# RPL_POWER_24V_REV3.net
KiCad netlist of a schematic drawn in Altium Designer
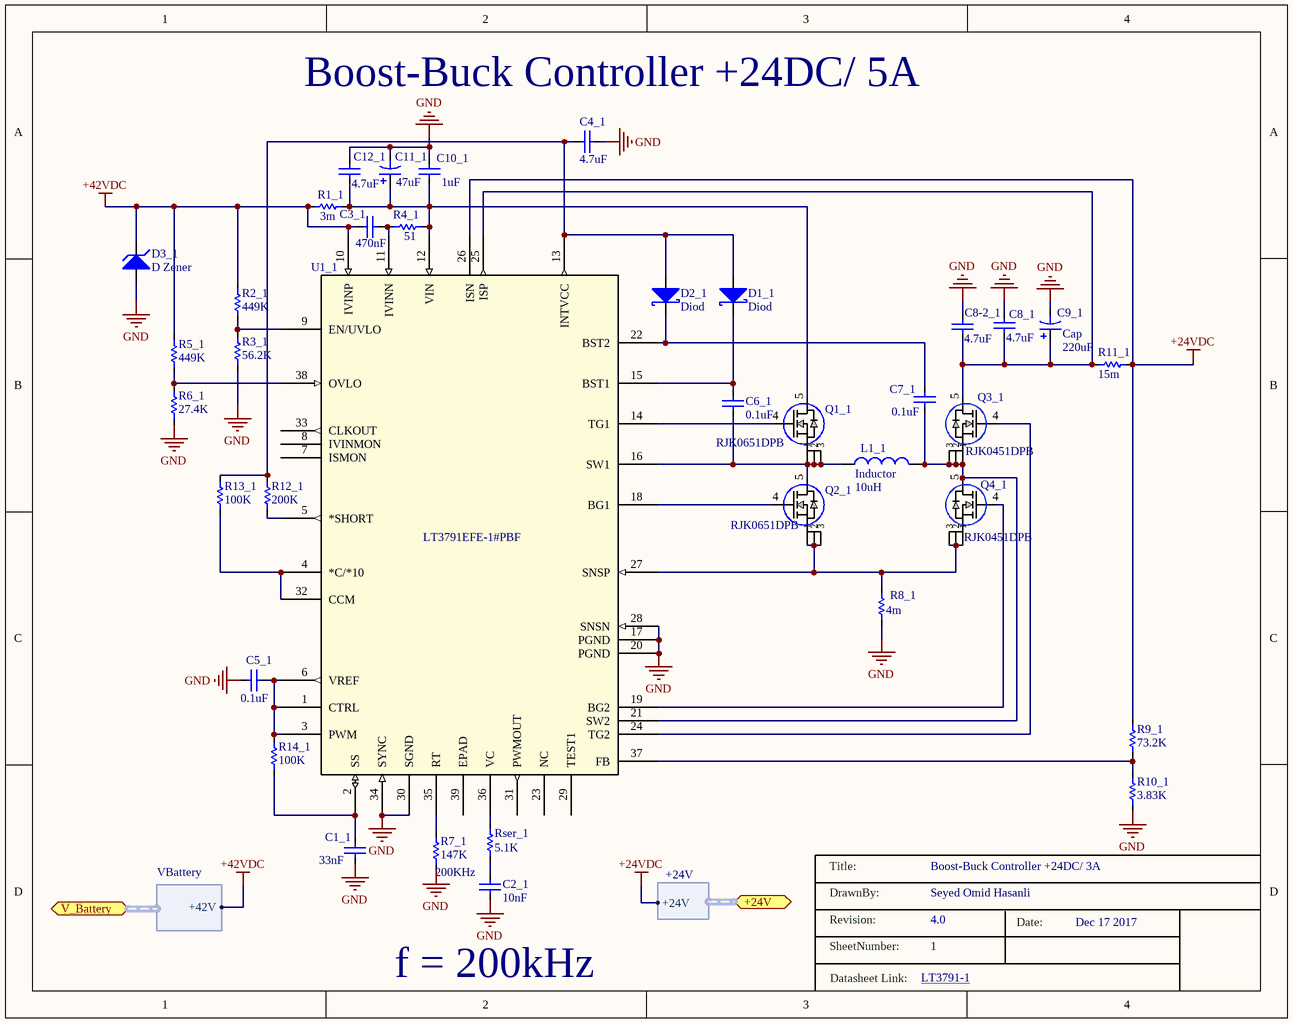
[diagram p0: RPL_POWER_24V_REV3.SchDoc]

(export (version "E")
  (design (tool "Eeschema 10.0.6"))
  (components
    (comp (ref "C1_1")
      (value "33nF")
      (footprint "C1206C475K5PACTU")
      (fields (field (name "Comment") "Cap"))
      (libsource (lib "Generic_Library") (part "Cap"))
    )
    (comp (ref "C2_1")
      (value "10nF")
      (footprint "C0805C475K9RACAUTO")
      (fields (field (name "Comment") "Rser=5.1K"))
      (libsource (lib "Generic_Library") (part "Cap"))
    )
    (comp (ref "C3_1")
      (value "470nF")
      (footprint "CAPs:C0805C475K9RACAUTO")
      (fields (field (name "Comment") "Cap"))
      (libsource (lib "Generic_Library") (part "Cap"))
    )
    (comp (ref "C4_1")
      (value "4.7uF")
      (footprint "CAPs:C0805C475K9RACAUTO")
      (fields (field (name "Comment") "Cap"))
      (libsource (lib "Generic_Library") (part "Cap"))
    )
    (comp (ref "C5_1")
      (value "0.1uF")
      (footprint "CAPs:C0805C475K9RACAUTO")
      (fields (field (name "Comment") "Cap"))
      (libsource (lib "Generic_Library") (part "Cap"))
    )
    (comp (ref "C6_1")
      (value "0.1uF")
      (footprint "CAPs:C0805C475K9RACAUTO")
      (fields (field (name "Comment") "Cap"))
      (libsource (lib "Generic_Library") (part "Cap"))
    )
    (comp (ref "C7_1")
      (value "0.1uF")
      (footprint "CAPs:C0805C475K9RACAUTO")
      (fields (field (name "Comment") "Cap"))
      (libsource (lib "Generic_Library") (part "Cap"))
    )
    (comp (ref "C8-2_1")
      (value "4.7uF")
      (footprint "CAPs:C1206C475K5PACTU")
      (fields (field (name "Comment") "Cap"))
      (libsource (lib "Generic_Library") (part "Cap"))
    )
    (comp (ref "C8_1")
      (value "4.7uF")
      (footprint "CAPs:C1206C475K5PACTU")
      (fields (field (name "Comment") "Cap"))
      (libsource (lib "Generic_Library") (part "Cap"))
    )
    (comp (ref "C9_1")
      (value "Cap")
      (footprint "EEE_FK1V221AP")
      (fields (field (name "ALTIUM_VALUE") "220uF"))
      (libsource (lib "Generic_Library") (part "Cap Elec"))
    )
    (comp (ref "C10_1")
      (value "1uF")
      (footprint "CAPs:C0805C475K9RACAUTO")
      (fields (field (name "Comment") "Cap"))
      (libsource (lib "Generic_Library") (part "Cap"))
    )
    (comp (ref "C11_1")
      (value "47uF")
      (footprint "EEH_ZC1K470P")
      (fields (field (name "Comment") "Cap"))
      (libsource (lib "Generic_Library") (part "Cap Elec"))
    )
    (comp (ref "C12_1")
      (value "4.7uF")
      (footprint "CAPs:C0805C475K9RACAUTO")
      (fields (field (name "Comment") "Cap"))
      (libsource (lib "Generic_Library") (part "Cap"))
    )
    (comp (ref "D1_1")
      (value "Diod")
      (footprint "Diods:SODFL250X80-2N")
      (libsource (lib "Generic_Library") (part "Diod"))
    )
    (comp (ref "D2_1")
      (value "Diod")
      (footprint "Diods:SODFL250X80-2N")
      (libsource (lib "Generic_Library") (part "Diod"))
    )
    (comp (ref "D3_1")
      (value "D Zener")
      (footprint "SMAJ30A-TP")
      (description "Zener Diode")
      (fields (field (name "PUBLISHER") "Altium Limited"))
      (libsource (lib "Generic_Library") (part "D Zener"))
    )
    (comp (ref "L1_1")
      (value "Inductor")
      (footprint "SER1360-103KLB")
      (fields (field (name "ALTIUM_VALUE") "10uH"))
      (libsource (lib "Generic_Library") (part "Inductor"))
    )
    (comp (ref "Q1_1")
      (value "RJK0651DPB")
      (footprint "RJK0651DPB:LFPAK")
      (description "Imported")
      (fields (field (name "MANUFACTURER_PART_NUMBER") "RJK0651DPB-00#J5"))
      (libsource (lib "Generic_Library") (part "RJK0651DPB-00#J5"))
    )
    (comp (ref "Q2_1")
      (value "RJK0651DPB")
      (footprint "RJK0651DPB:LFPAK")
      (description "Imported")
      (fields (field (name "MANUFACTURER_PART_NUMBER") "RJK0651DPB-00#J5"))
      (libsource (lib "Generic_Library") (part "RJK0651DPB-00#J5"))
    )
    (comp (ref "Q3_1")
      (value "RJK0451DPB")
      (footprint "RJK0451DPB:LFPAK")
      (description "Imported")
      (fields (field (name "MANUFACTURER_PART_NUMBER") "RJK0451DPB-00#J5"))
      (libsource (lib "Generic_Library") (part "RJK0451DPB-00#J5"))
    )
    (comp (ref "Q4_1")
      (value "RJK0451DPB")
      (footprint "RJK0451DPB:LFPAK")
      (description "Imported")
      (fields (field (name "MANUFACTURER_PART_NUMBER") "RJK0451DPB-00#J5"))
      (libsource (lib "Generic_Library") (part "RJK0451DPB-00#J5"))
    )
    (comp (ref "R1_1")
      (value "3m")
      (footprint "Resistors:WSL12063L000FEA(1206)")
      (fields (field (name "Comment") "Res"))
      (libsource (lib "Generic_Library") (part "Res"))
    )
    (comp (ref "R2_1")
      (value "449K")
      (footprint "SMD Resistors:RES 0805")
      (fields (field (name "Comment") "Res"))
      (libsource (lib "Generic_Library") (part "Res"))
    )
    (comp (ref "R3_1")
      (value "56.2K")
      (footprint "SMD Resistors:RES 0805")
      (fields (field (name "Comment") "Res"))
      (libsource (lib "Generic_Library") (part "Res"))
    )
    (comp (ref "R4_1")
      (value "51")
      (footprint "SMD Resistors:RES 0805")
      (fields (field (name "Comment") "Res"))
      (libsource (lib "Generic_Library") (part "Res"))
    )
    (comp (ref "R5_1")
      (value "449K")
      (footprint "Resistors:PTN1206E4993BBT1(1206)")
      (fields (field (name "Comment") "Res"))
      (libsource (lib "Generic_Library") (part "Res"))
    )
    (comp (ref "R6_1")
      (value "27.4K")
      (footprint "SMD Resistors:RES 0805")
      (fields (field (name "Comment") "Res"))
      (libsource (lib "Generic_Library") (part "Res"))
    )
    (comp (ref "R7_1")
      (value "200KHz")
      (footprint "SMD Resistors:RES 0805")
      (fields (field (name "ALTIUM_VALUE") "147K"))
      (libsource (lib "Generic_Library") (part "Res"))
    )
    (comp (ref "R8_1")
      (value "4m")
      (footprint "SMD Resistors:RES 0805")
      (fields (field (name "Comment") "Res"))
      (libsource (lib "Generic_Library") (part "Res"))
    )
    (comp (ref "R9_1")
      (value "73.2K")
      (footprint "SMD Resistors:RES 0805")
      (fields (field (name "Comment") "Res"))
      (libsource (lib "Generic_Library") (part "Res"))
    )
    (comp (ref "R10_1")
      (value "3.83K")
      (footprint "SMD Resistors:RES 0805")
      (fields (field (name "Comment") "Res"))
      (libsource (lib "Generic_Library") (part "Res"))
    )
    (comp (ref "R11_1")
      (value "15m")
      (footprint "Resistors:WSL2010R0150FEA(2010)")
      (fields (field (name "Comment") "Res"))
      (libsource (lib "Generic_Library") (part "Res"))
    )
    (comp (ref "R12_1")
      (value "200K")
      (footprint "SMD Resistors:RES 0805")
      (fields (field (name "Comment") "Res"))
      (libsource (lib "Generic_Library") (part "Res"))
    )
    (comp (ref "R13_1")
      (value "100K")
      (footprint "SMD Resistors:RES 0805")
      (fields (field (name "Comment") "Res"))
      (libsource (lib "Generic_Library") (part "Res"))
    )
    (comp (ref "R14_1")
      (value "100K")
      (footprint "SMD Resistors:RES 0805")
      (fields (field (name "Comment") "Res"))
      (libsource (lib "Generic_Library") (part "Res"))
    )
    (comp (ref "Rser_1")
      (value "5.1K")
      (footprint "SMD Resistors:RES 0805")
      (fields (field (name "Comment") "Res"))
      (libsource (lib "Generic_Library") (part "Res"))
    )
    (comp (ref "U1_1")
      (value "LT3791EFE-1#PBF")
      (footprint "LT3791-1:TSSOP-38_FE/AA")
      (description "Imported")
      (fields (field (name "MANUFACTURER_PART_NUMBER") "lt3791efe-1#pbf"))
      (libsource (lib "Generic_Library") (part "LT3791EFE-1#PBF"))
    )
  )
  (nets
    (net (code "3") (name "+24VDC") (class "Default")
      (node (ref "R11_1") (pin "2") (pinfunction "2_2") (pintype "passive"))
      (node (ref "R9_1") (pin "2") (pinfunction "2_2") (pintype "passive"))
      (node (ref "U1_1") (pin "26") (pinfunction "ISN_26") (pintype "passive"))
    )
    (net (code "4") (name "+42VDC") (class "Default")
      (node (ref "C3_1") (pin "1") (pinfunction "1_1") (pintype "passive"))
      (node (ref "D3_1") (pin "2") (pinfunction "K_2") (pintype "passive"))
      (node (ref "R1_1") (pin "1") (pinfunction "1_1") (pintype "passive"))
      (node (ref "R2_1") (pin "2") (pinfunction "2_2") (pintype "passive"))
      (node (ref "R5_1") (pin "2") (pinfunction "2_2") (pintype "passive"))
      (node (ref "U1_1") (pin "10") (pinfunction "IVINP_10") (pintype "input"))
    )
    (net (code "7") (name "GND") (class "Default")
      (node (ref "C10_1") (pin "2") (pinfunction "2_2") (pintype "passive"))
      (node (ref "C11_1") (pin "2") (pinfunction "2_2") (pintype "passive"))
      (node (ref "C12_1") (pin "2") (pinfunction "2_2") (pintype "passive"))
      (node (ref "C1_1") (pin "1") (pinfunction "1_1") (pintype "passive"))
      (node (ref "C2_1") (pin "1") (pinfunction "1_1") (pintype "passive"))
      (node (ref "C4_1") (pin "1") (pinfunction "1_1") (pintype "passive"))
      (node (ref "C5_1") (pin "1") (pinfunction "1_1") (pintype "passive"))
      (node (ref "C8-2_1") (pin "2") (pinfunction "2_2") (pintype "passive"))
      (node (ref "C8_1") (pin "2") (pinfunction "2_2") (pintype "passive"))
      (node (ref "C9_1") (pin "2") (pinfunction "2_2") (pintype "passive"))
      (node (ref "D3_1") (pin "1") (pinfunction "A_1") (pintype "passive"))
      (node (ref "R10_1") (pin "1") (pinfunction "1_1") (pintype "passive"))
      (node (ref "R3_1") (pin "1") (pinfunction "1_1") (pintype "passive"))
      (node (ref "R6_1") (pin "1") (pinfunction "1_1") (pintype "passive"))
      (node (ref "R7_1") (pin "1") (pinfunction "1_1") (pintype "passive"))
      (node (ref "R8_1") (pin "1") (pinfunction "1_1") (pintype "passive"))
      (node (ref "U1_1") (pin "17") (pinfunction "PGND_17") (pintype "power_in"))
      (node (ref "U1_1") (pin "20") (pinfunction "PGND_20") (pintype "power_in"))
      (node (ref "U1_1") (pin "28") (pinfunction "SNSN_28") (pintype "input"))
      (node (ref "U1_1") (pin "30") (pinfunction "SGND_30") (pintype "power_in"))
      (node (ref "U1_1") (pin "34") (pinfunction "SYNC_34") (pintype "input"))
    )
    (net (code "8") (name "Net-(C2_1-Pad2)") (class "Default")
      (node (ref "C2_1") (pin "2") (pinfunction "2_2") (pintype "passive"))
      (node (ref "Rser_1") (pin "1") (pinfunction "1_1") (pintype "passive"))
    )
    (net (code "9") (name "Net-(D1_1-A)") (class "Default")
      (node (ref "C4_1") (pin "2") (pinfunction "2_2") (pintype "passive"))
      (node (ref "D1_1") (pin "1") (pinfunction "A_1") (pintype "passive"))
      (node (ref "D2_1") (pin "1") (pinfunction "A_1") (pintype "passive"))
      (node (ref "R12_1") (pin "2") (pinfunction "2_2") (pintype "passive"))
      (node (ref "R13_1") (pin "2") (pinfunction "2_2") (pintype "passive"))
      (node (ref "U1_1") (pin "13") (pinfunction "INTVCC_13") (pintype "output"))
    )
    (net (code "10") (name "Net-(D1_1-K)") (class "Default")
      (node (ref "C6_1") (pin "2") (pinfunction "2_2") (pintype "passive"))
      (node (ref "D1_1") (pin "2") (pinfunction "K_2") (pintype "passive"))
      (node (ref "U1_1") (pin "15") (pinfunction "BST1_15") (pintype "passive"))
    )
    (net (code "11") (name "Net-(D2_1-K)") (class "Default")
      (node (ref "C7_1") (pin "2") (pinfunction "2_2") (pintype "passive"))
      (node (ref "D2_1") (pin "2") (pinfunction "K_2") (pintype "passive"))
      (node (ref "U1_1") (pin "22") (pinfunction "BST2_22") (pintype "passive"))
    )
    (net (code "12") (name "Net-(U1_1-*C{slash}*10)") (class "Default")
      (node (ref "R13_1") (pin "1") (pinfunction "1_1") (pintype "passive"))
      (node (ref "U1_1") (pin "32") (pinfunction "CCM_32") (pintype "passive"))
      (node (ref "U1_1") (pin "4") (pinfunction "*C/*10_4") (pintype "passive"))
    )
    (net (code "13") (name "Net-(U1_1-*SHORT)") (class "Default")
      (node (ref "R12_1") (pin "1") (pinfunction "1_1") (pintype "passive"))
      (node (ref "U1_1") (pin "5") (pinfunction "*SHORT_5") (pintype "output"))
    )
    (net (code "14") (name "Net-(U1_1-BG1)") (class "Default")
      (node (ref "Q2_1") (pin "4") (pinfunction "4_4") (pintype "passive"))
      (node (ref "U1_1") (pin "18") (pinfunction "BG1_18") (pintype "passive"))
    )
    (net (code "15") (name "Net-(U1_1-BG2)") (class "Default")
      (node (ref "Q4_1") (pin "4") (pinfunction "4_4") (pintype "passive"))
      (node (ref "U1_1") (pin "19") (pinfunction "BG2_19") (pintype "passive"))
    )
    (net (code "16") (name "Net-(U1_1-CTRL)") (class "Default")
      (node (ref "C5_1") (pin "2") (pinfunction "2_2") (pintype "passive"))
      (node (ref "R14_1") (pin "2") (pinfunction "2_2") (pintype "passive"))
      (node (ref "U1_1") (pin "1") (pinfunction "CTRL_1") (pintype "passive"))
      (node (ref "U1_1") (pin "3") (pinfunction "PWM_3") (pintype "passive"))
      (node (ref "U1_1") (pin "6") (pinfunction "VREF_6") (pintype "output"))
    )
    (net (code "17") (name "Net-(U1_1-EN{slash}UVLO)") (class "Default")
      (node (ref "R2_1") (pin "1") (pinfunction "1_1") (pintype "passive"))
      (node (ref "R3_1") (pin "2") (pinfunction "2_2") (pintype "passive"))
      (node (ref "U1_1") (pin "9") (pinfunction "EN/UVLO_9") (pintype "passive"))
    )
    (net (code "18") (name "Net-(U1_1-FB)") (class "Default")
      (node (ref "R10_1") (pin "2") (pinfunction "2_2") (pintype "passive"))
      (node (ref "R9_1") (pin "1") (pinfunction "1_1") (pintype "passive"))
      (node (ref "U1_1") (pin "37") (pinfunction "FB_37") (pintype "passive"))
    )
    (net (code "19") (name "Net-(U1_1-ISP)") (class "Default")
      (node (ref "C8-2_1") (pin "1") (pinfunction "1_1") (pintype "passive"))
      (node (ref "C8_1") (pin "1") (pinfunction "1_1") (pintype "passive"))
      (node (ref "C9_1") (pin "1") (pinfunction "1_1") (pintype "passive"))
      (node (ref "Q3_1") (pin "5") (pinfunction "5_5") (pintype "passive"))
      (node (ref "R11_1") (pin "1") (pinfunction "1_1") (pintype "passive"))
      (node (ref "U1_1") (pin "25") (pinfunction "ISP_25") (pintype "output"))
    )
    (net (code "20") (name "Net-(U1_1-IVINN)") (class "Default")
      (node (ref "C3_1") (pin "2") (pinfunction "2_2") (pintype "passive"))
      (node (ref "R4_1") (pin "1") (pinfunction "1_1") (pintype "passive"))
      (node (ref "U1_1") (pin "11") (pinfunction "IVINN_11") (pintype "input"))
    )
    (net (code "21") (name "Net-(U1_1-OVLO)") (class "Default")
      (node (ref "R5_1") (pin "1") (pinfunction "1_1") (pintype "passive"))
      (node (ref "R6_1") (pin "2") (pinfunction "2_2") (pintype "passive"))
      (node (ref "U1_1") (pin "38") (pinfunction "OVLO_38") (pintype "input"))
    )
    (net (code "22") (name "Net-(U1_1-RT)") (class "Default")
      (node (ref "R7_1") (pin "2") (pinfunction "2_2") (pintype "passive"))
      (node (ref "U1_1") (pin "35") (pinfunction "RT_35") (pintype "passive"))
    )
    (net (code "23") (name "Net-(U1_1-SNSP)") (class "Default")
      (node (ref "Q2_1") (pin "1") (pinfunction "1_1") (pintype "passive"))
      (node (ref "Q2_1") (pin "2") (pinfunction "2_2") (pintype "passive"))
      (node (ref "Q2_1") (pin "3") (pinfunction "3_3") (pintype "passive"))
      (node (ref "Q4_1") (pin "1") (pinfunction "1_1") (pintype "passive"))
      (node (ref "Q4_1") (pin "2") (pinfunction "2_2") (pintype "passive"))
      (node (ref "Q4_1") (pin "3") (pinfunction "3_3") (pintype "passive"))
      (node (ref "R8_1") (pin "2") (pinfunction "2_2") (pintype "passive"))
      (node (ref "U1_1") (pin "27") (pinfunction "SNSP_27") (pintype "input"))
    )
    (net (code "24") (name "Net-(U1_1-SS)") (class "Default")
      (node (ref "C1_1") (pin "2") (pinfunction "2_2") (pintype "passive"))
      (node (ref "R14_1") (pin "1") (pinfunction "1_1") (pintype "passive"))
      (node (ref "U1_1") (pin "2") (pinfunction "SS_2") (pintype "bidirectional"))
    )
    (net (code "25") (name "Net-(U1_1-SW1)") (class "Default")
      (node (ref "C6_1") (pin "1") (pinfunction "1_1") (pintype "passive"))
      (node (ref "L1_1") (pin "1") (pinfunction "1_1") (pintype "passive"))
      (node (ref "Q1_1") (pin "1") (pinfunction "1_1") (pintype "passive"))
      (node (ref "Q1_1") (pin "2") (pinfunction "2_2") (pintype "passive"))
      (node (ref "Q1_1") (pin "3") (pinfunction "3_3") (pintype "passive"))
      (node (ref "Q2_1") (pin "5") (pinfunction "5_5") (pintype "passive"))
      (node (ref "U1_1") (pin "16") (pinfunction "SW1_16") (pintype "passive"))
    )
    (net (code "26") (name "Net-(U1_1-SW2)") (class "Default")
      (node (ref "C7_1") (pin "1") (pinfunction "1_1") (pintype "passive"))
      (node (ref "L1_1") (pin "2") (pinfunction "2_2") (pintype "passive"))
      (node (ref "Q3_1") (pin "1") (pinfunction "1_1") (pintype "passive"))
      (node (ref "Q3_1") (pin "2") (pinfunction "2_2") (pintype "passive"))
      (node (ref "Q3_1") (pin "3") (pinfunction "3_3") (pintype "passive"))
      (node (ref "Q4_1") (pin "5") (pinfunction "5_5") (pintype "passive"))
      (node (ref "U1_1") (pin "21") (pinfunction "SW2_21") (pintype "passive"))
    )
    (net (code "27") (name "Net-(U1_1-TG1)") (class "Default")
      (node (ref "Q1_1") (pin "4") (pinfunction "4_4") (pintype "passive"))
      (node (ref "U1_1") (pin "14") (pinfunction "TG1_14") (pintype "passive"))
    )
    (net (code "28") (name "Net-(U1_1-TG2)") (class "Default")
      (node (ref "Q3_1") (pin "4") (pinfunction "4_4") (pintype "passive"))
      (node (ref "U1_1") (pin "24") (pinfunction "TG2_24") (pintype "passive"))
    )
    (net (code "29") (name "Net-(U1_1-VC)") (class "Default")
      (node (ref "Rser_1") (pin "2") (pinfunction "2_2") (pintype "passive"))
      (node (ref "U1_1") (pin "36") (pinfunction "VC_36") (pintype "passive"))
    )
    (net (code "30") (name "Net-(U1_1-VIN)") (class "Default")
      (node (ref "C10_1") (pin "1") (pinfunction "1_1") (pintype "passive"))
      (node (ref "C11_1") (pin "1") (pinfunction "1_1") (pintype "passive"))
      (node (ref "C12_1") (pin "1") (pinfunction "1_1") (pintype "passive"))
      (node (ref "Q1_1") (pin "5") (pinfunction "5_5") (pintype "passive"))
      (node (ref "R1_1") (pin "2") (pinfunction "2_2") (pintype "passive"))
      (node (ref "R4_1") (pin "2") (pinfunction "2_2") (pintype "passive"))
      (node (ref "U1_1") (pin "12") (pinfunction "VIN_12") (pintype "input"))
    )
    (net (code "31") (name "unconnected-(U1_1-CLKOUT-Pad33)") (class "Default")
      (node (ref "U1_1") (pin "33") (pinfunction "CLKOUT_33") (pintype "output"))
    )
    (net (code "32") (name "unconnected-(U1_1-EPAD-Pad39)") (class "Default")
      (node (ref "U1_1") (pin "39") (pinfunction "EPAD_39") (pintype "passive"))
    )
    (net (code "33") (name "unconnected-(U1_1-ISMON-Pad7)") (class "Default")
      (node (ref "U1_1") (pin "7") (pinfunction "ISMON_7") (pintype "passive"))
    )
    (net (code "34") (name "unconnected-(U1_1-IVINMON-Pad8)") (class "Default")
      (node (ref "U1_1") (pin "8") (pinfunction "IVINMON_8") (pintype "passive"))
    )
    (net (code "35") (name "unconnected-(U1_1-NC-Pad23)") (class "Default")
      (node (ref "U1_1") (pin "23") (pinfunction "NC_23") (pintype "passive"))
    )
    (net (code "36") (name "unconnected-(U1_1-PWMOUT-Pad31)") (class "Default")
      (node (ref "U1_1") (pin "31") (pinfunction "PWMOUT_31") (pintype "output"))
    )
    (net (code "37") (name "unconnected-(U1_1-TEST1-Pad29)") (class "Default")
      (node (ref "U1_1") (pin "29") (pinfunction "TEST1_29") (pintype "passive"))
    )
  )
)
